# USB_OTG_FS.net
KiCad netlist of a schematic drawn in Altium Designer
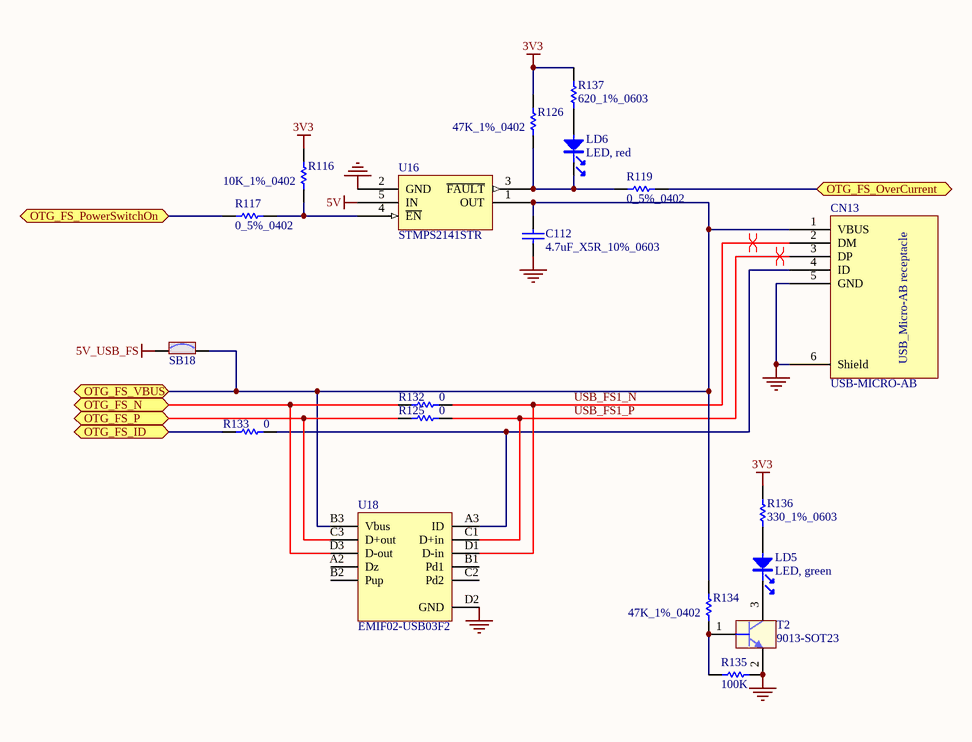
[diagram p0: USB_OTG_FS.SchDoc]

(export (version "E")
  (design (tool "Eeschema 10.0.6"))
  (components
    (comp (ref "C112")
      (value "4.7uF_X5R_10%_0603")
      (footprint "0603C")
      (description "Capacitor,4.7uF,16V, X5R,10%,0603,YAGEO")
      (libsource (lib "MCD_TOOLS") (part "Cap_4.7uF_X5R_10%_0603"))
    )
    (comp (ref "CN13")
      (value "USB-MICRO-AB")
      (footprint "USB-MICRO-AB")
      (description "USB-MICRO-AB, 47590-0001, SMT, MOLEX")
      (libsource (lib "MCD_TOOLS") (part "USB-MICRO-AB"))
    )
    (comp (ref "LD5")
      (value "LED, green")
      (footprint "0603D")
      (description "LED,green,0603,19-213SYGC/S530-E2/TR8,everlight")
      (libsource (lib "MCD_TOOLS") (part "LED_green"))
    )
    (comp (ref "LD6")
      (value "LED, red")
      (footprint "0603D")
      (description "LED,red,0603,19-213-R6C-AP1Q2B/3T,everlight")
      (libsource (lib "MCD_TOOLS") (part "LED_red"))
    )
    (comp (ref "R116")
      (value "10K_1%_0402")
      (footprint "0402R")
      (description "Resistor,10K,0402,1%,YAGEO")
      (libsource (lib "MCD_TOOLS") (part "Res_10K_1%_0402"))
    )
    (comp (ref "R117")
      (value "0_5%_0402")
      (footprint "0402R")
      (description "Resistor,0,0402,5%,YAGEO")
      (libsource (lib "MCD_TOOLS") (part "Res_0_5%_0402"))
    )
    (comp (ref "R119")
      (value "0_5%_0402")
      (footprint "0402R")
      (description "Resistor,0,0402,5%,YAGEO")
      (libsource (lib "MCD_TOOLS") (part "Res_0_5%_0402"))
    )
    (comp (ref "R125")
      (value "0")
      (footprint "0402R")
      (description "Resistor,0,0402,5%,YAGEO")
      (libsource (lib "MCD_TOOLS") (part "Res_0_5%_0402"))
    )
    (comp (ref "R126")
      (value "47K_1%_0402")
      (footprint "0402R")
      (description "Resistor,47K,0402,1%,YAGEO")
      (libsource (lib "MCD_TOOLS") (part "Res_47K_1%_0402"))
    )
    (comp (ref "R132")
      (value "0")
      (footprint "0402R")
      (description "Resistor,0,0402,5%,YAGEO")
      (libsource (lib "MCD_TOOLS") (part "Res_0_5%_0402"))
    )
    (comp (ref "R133")
      (value "0")
      (footprint "0402R")
      (description "Resistor,0,0402,5%,YAGEO")
      (libsource (lib "MCD_TOOLS") (part "Res_0_5%_0402"))
    )
    (comp (ref "R134")
      (value "47K_1%_0402")
      (footprint "0402R")
      (description "Resistor,47K,0402,1%,YAGEO")
      (libsource (lib "MCD_TOOLS") (part "Res_47K_1%_0402"))
    )
    (comp (ref "R135")
      (value "100K")
      (footprint "0402R")
      (description "Resistor,100K,0402,1%,YAGEO")
      (libsource (lib "MCD_TOOLS") (part "Res_100K_1%_0402"))
    )
    (comp (ref "R136")
      (value "330_1%_0603")
      (footprint "0603R")
      (description "Resistor,330,0603,1%,YAGEO")
      (libsource (lib "MCD_TOOLS") (part "Res_330_1%_0603"))
    )
    (comp (ref "R137")
      (value "620_1%_0603")
      (footprint "0603R")
      (description "Resistor,620,0603,1%,VISHAY")
      (libsource (lib "MCD_TOOLS") (part "Res_620_1%_0603"))
    )
    (comp (ref "SB18")
      (value "Solder Bridge ON")
      (footprint "JP2_SMD")
      (libsource (lib "MCD_TOOLS") (part "SB_ON"))
    )
    (comp (ref "T2")
      (value "9013-SOT23")
      (footprint "SOT23")
      (description "NPN Bipolar Transistor, SOT-23 Footprint")
      (libsource (lib "MCD_TOOLS") (part "9013-SOT23"))
    )
    (comp (ref "U16")
      (value "STMPS2141STR")
      (footprint "SOT23-5L")
      (description "Enhanced single channel power switches")
      (libsource (lib "MCD_TOOLS") (part "STMPS2141STR"))
    )
    (comp (ref "U18")
      (value "EMIF02-USB03F2")
      (footprint "Flip Chip")
      (description "2-line IPAD, EMI filter including ESD protection")
      (libsource (lib "MCD_TOOLS") (part "EMIF02-USB03F2"))
    )
  )
  (nets
    (net (code "1") (name "/OTG_FS_ID") (class "Default")
      (node (ref "R133") (pin "1") (pinfunction "1_1") (pintype "passive"))
    )
    (net (code "2") (name "/OTG_FS_N") (class "Default")
      (node (ref "R132") (pin "1") (pinfunction "1_1") (pintype "passive"))
      (node (ref "U18") (pin "D3") (pinfunction "D-out_D3") (pintype "passive"))
    )
    (net (code "3") (name "/OTG_FS_OverCurrent") (class "Default")
      (node (ref "R119") (pin "2") (pinfunction "2_2") (pintype "passive"))
    )
    (net (code "4") (name "/OTG_FS_P") (class "Default")
      (node (ref "R125") (pin "1") (pinfunction "1_1") (pintype "passive"))
      (node (ref "U18") (pin "C3") (pinfunction "D+out_C3") (pintype "passive"))
    )
    (net (code "5") (name "/OTG_FS_PowerSwitchOn") (class "Default")
      (node (ref "R117") (pin "1") (pinfunction "1_1") (pintype "passive"))
    )
    (net (code "6") (name "/OTG_FS_VBUS") (class "Default")
      (node (ref "C112") (pin "2") (pinfunction "2_2") (pintype "passive"))
      (node (ref "CN13") (pin "1") (pinfunction "VBUS_1") (pintype "passive"))
      (node (ref "R134") (pin "2") (pinfunction "2_2") (pintype "passive"))
      (node (ref "SB18") (pin "2") (pinfunction "2_2") (pintype "passive"))
      (node (ref "U16") (pin "1") (pinfunction "OUT_1") (pintype "passive"))
      (node (ref "U18") (pin "B3") (pinfunction "Vbus_B3") (pintype "passive"))
    )
    (net (code "7") (name "/USB_FS1_N") (class "Default")
      (node (ref "CN13") (pin "2") (pinfunction "DM_2") (pintype "passive"))
      (node (ref "R132") (pin "2") (pinfunction "2_2") (pintype "passive"))
      (node (ref "U18") (pin "D1") (pinfunction "D-in_D1") (pintype "passive"))
    )
    (net (code "8") (name "/USB_FS1_P") (class "Default")
      (node (ref "CN13") (pin "3") (pinfunction "DP_3") (pintype "passive"))
      (node (ref "R125") (pin "2") (pinfunction "2_2") (pintype "passive"))
      (node (ref "U18") (pin "C1") (pinfunction "D+in_C1") (pintype "passive"))
    )
    (net (code "9") (name "3V3") (class "Default")
      (node (ref "R116") (pin "2") (pinfunction "2_2") (pintype "passive"))
      (node (ref "R126") (pin "2") (pinfunction "2_2") (pintype "passive"))
      (node (ref "R136") (pin "2") (pinfunction "2_2") (pintype "passive"))
      (node (ref "R137") (pin "2") (pinfunction "2_2") (pintype "passive"))
    )
    (net (code "10") (name "5V") (class "Default")
      (node (ref "U16") (pin "5") (pinfunction "IN_5") (pintype "passive"))
    )
    (net (code "11") (name "5V_USB_FS") (class "Default")
      (node (ref "SB18") (pin "1") (pinfunction "1_1") (pintype "passive"))
    )
    (net (code "12") (name "GND") (class "Default")
      (node (ref "C112") (pin "1") (pinfunction "1_1") (pintype "passive"))
      (node (ref "CN13") (pin "5") (pinfunction "GND_5") (pintype "passive"))
      (node (ref "CN13") (pin "6") (pinfunction "Shield_6") (pintype "passive"))
      (node (ref "R135") (pin "2") (pinfunction "2_2") (pintype "passive"))
      (node (ref "T2") (pin "2") (pinfunction "E_2") (pintype "passive"))
      (node (ref "U16") (pin "2") (pinfunction "GND_2") (pintype "passive"))
      (node (ref "U18") (pin "D2") (pinfunction "GND_D2") (pintype "passive"))
    )
    (net (code "13") (name "Net-(CN13-ID)") (class "Default")
      (node (ref "CN13") (pin "4") (pinfunction "ID_4") (pintype "passive"))
      (node (ref "R133") (pin "2") (pinfunction "2_2") (pintype "passive"))
      (node (ref "U18") (pin "A3") (pinfunction "ID_A3") (pintype "passive"))
    )
    (net (code "14") (name "Net-(LD5-Pad1)") (class "Default")
      (node (ref "LD5") (pin "1") (pintype "passive"))
      (node (ref "R136") (pin "1") (pinfunction "1_1") (pintype "passive"))
    )
    (net (code "15") (name "Net-(LD6-Pad1)") (class "Default")
      (node (ref "LD6") (pin "1") (pintype "passive"))
      (node (ref "R137") (pin "1") (pinfunction "1_1") (pintype "passive"))
    )
    (net (code "16") (name "Net-(T2-B)") (class "Default")
      (node (ref "R134") (pin "1") (pinfunction "1_1") (pintype "passive"))
      (node (ref "R135") (pin "1") (pinfunction "1_1") (pintype "passive"))
      (node (ref "T2") (pin "1") (pinfunction "B_1") (pintype "passive"))
    )
    (net (code "17") (name "Net-(T2-C)") (class "Default")
      (node (ref "LD5") (pin "2") (pintype "passive"))
      (node (ref "T2") (pin "3") (pinfunction "C_3") (pintype "passive"))
    )
    (net (code "18") (name "Net-(U16-~{EN})") (class "Default")
      (node (ref "R116") (pin "1") (pinfunction "1_1") (pintype "passive"))
      (node (ref "R117") (pin "2") (pinfunction "2_2") (pintype "passive"))
      (node (ref "U16") (pin "4") (pinfunction "~{EN}_4") (pintype "input"))
    )
    (net (code "19") (name "Net-(U16-~{FAULT})") (class "Default")
      (node (ref "LD6") (pin "2") (pintype "passive"))
      (node (ref "R119") (pin "1") (pinfunction "1_1") (pintype "passive"))
      (node (ref "R126") (pin "1") (pinfunction "1_1") (pintype "passive"))
      (node (ref "U16") (pin "3") (pinfunction "~{FAULT}_3") (pintype "output"))
    )
    (net (code "20") (name "unconnected-(U18-Dz-PadA2)") (class "Default")
      (node (ref "U18") (pin "A2") (pinfunction "Dz_A2") (pintype "passive"))
    )
    (net (code "21") (name "unconnected-(U18-Pd1-PadB1)") (class "Default")
      (node (ref "U18") (pin "B1") (pinfunction "Pd1_B1") (pintype "passive"))
    )
    (net (code "22") (name "unconnected-(U18-Pd2-PadC2)") (class "Default")
      (node (ref "U18") (pin "C2") (pinfunction "Pd2_C2") (pintype "passive"))
    )
    (net (code "23") (name "unconnected-(U18-Pup-PadB2)") (class "Default")
      (node (ref "U18") (pin "B2") (pinfunction "Pup_B2") (pintype "passive"))
    )
  )
)
